# SRM32_Pi_HAT.net
KiCad netlist of a schematic drawn in Altium Designer
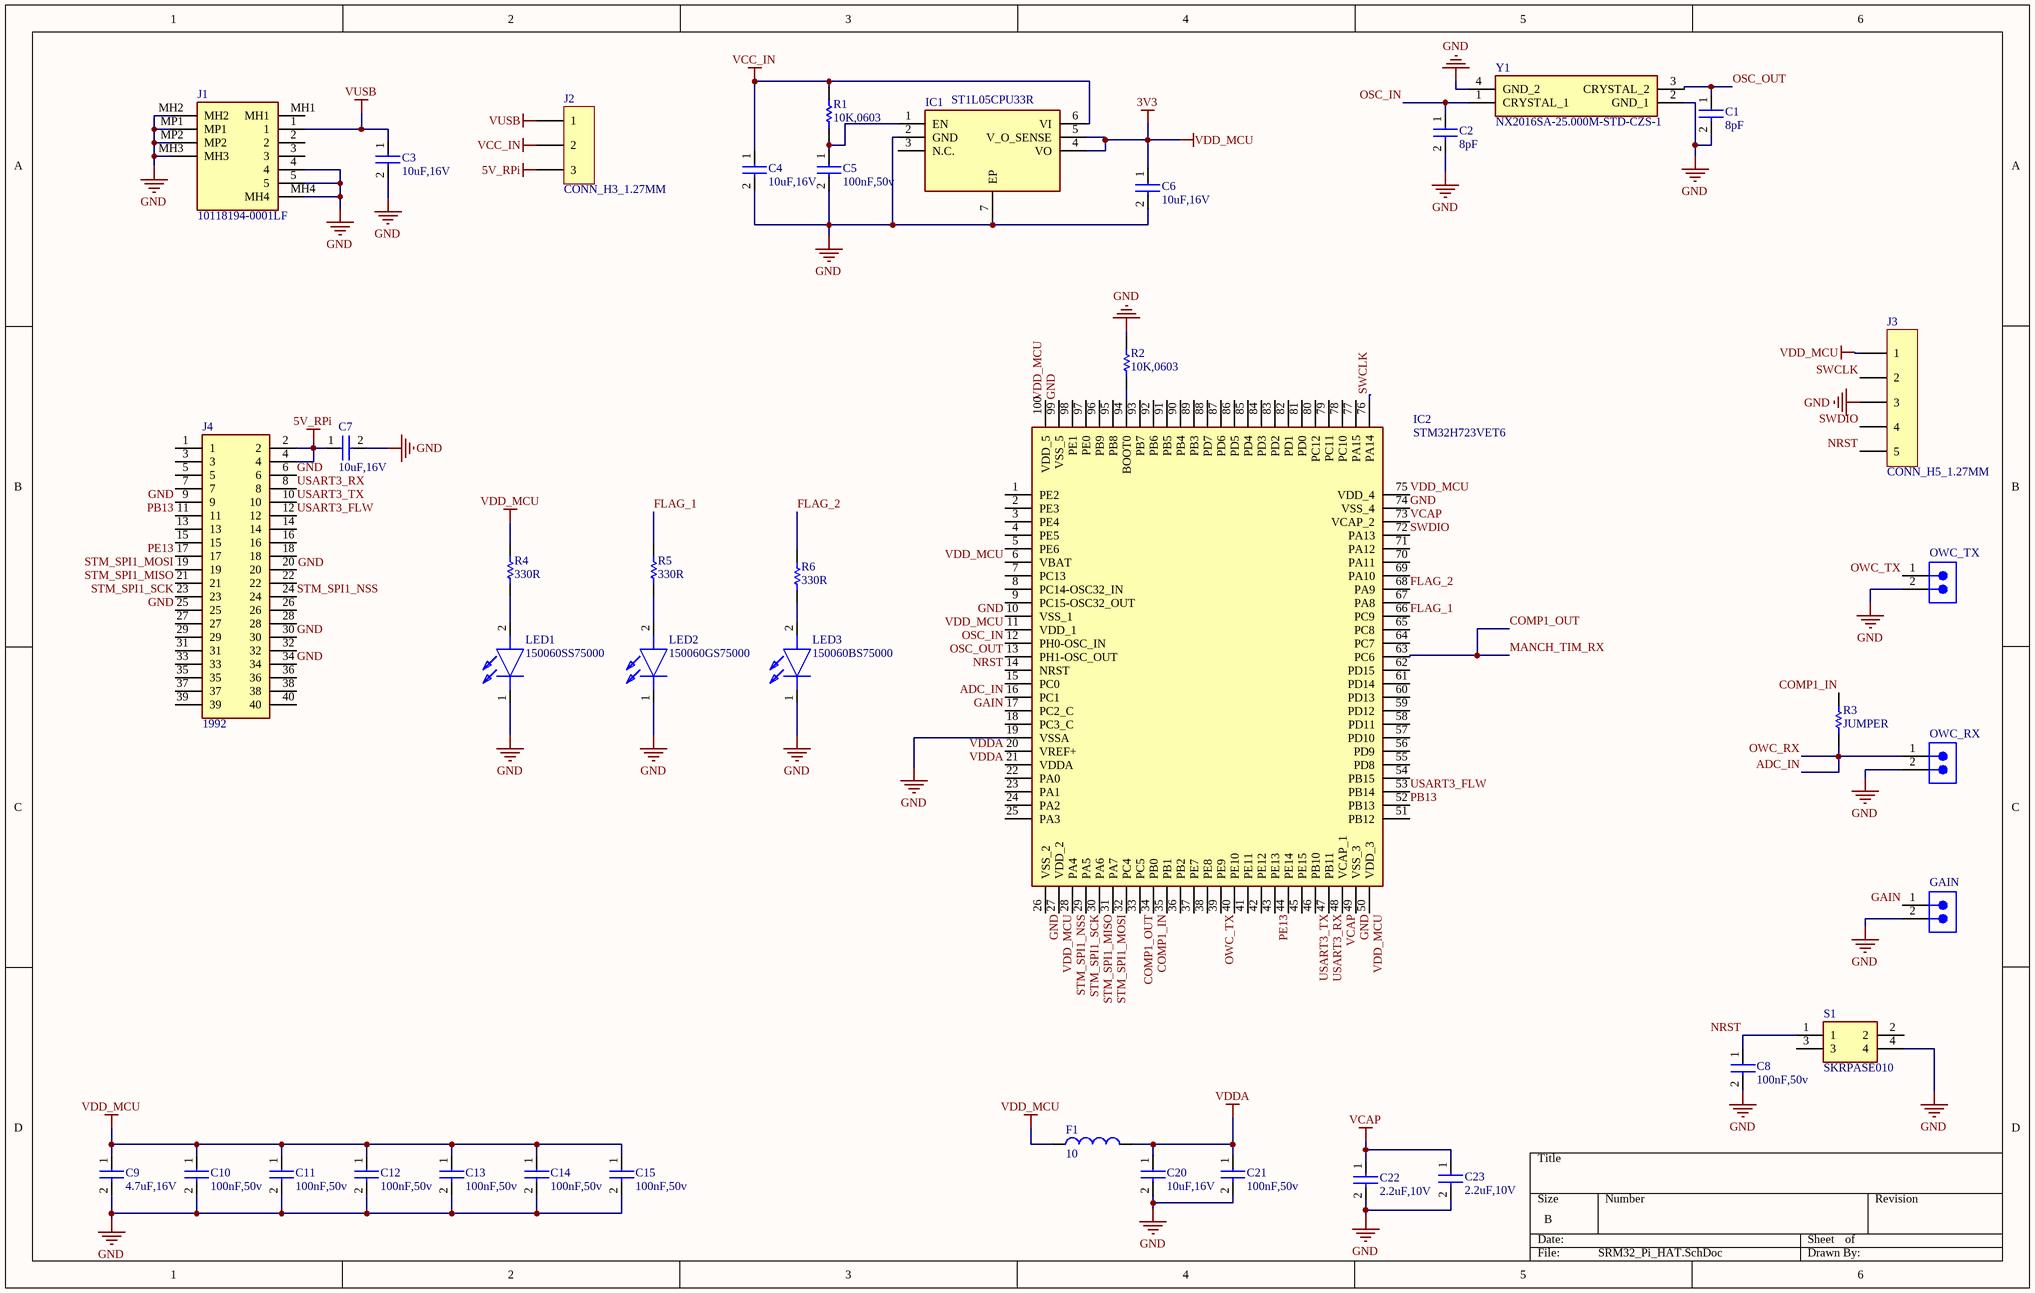
[diagram p0: SRM32_Pi_HAT.SchDoc]

(export (version "E")
  (design (tool "Eeschema 10.0.6"))
  (components
    (comp (ref "C1")
      (value "8pF")
      (footprint "CAP0603_")
      (description "Multilayer Ceramic Capacitors MLCC - SMD/SMT WCAP-CSGP 100V 4.7pF 0603 .25pFTol")
      (libsource (lib "RLC_COMPONENTS") (part "C0603-4.7pF-100v"))
    )
    (comp (ref "C2")
      (value "8pF")
      (footprint "CAP0603_")
      (description "Multilayer Ceramic Capacitors MLCC - SMD/SMT WCAP-CSGP 100V 4.7pF 0603 .25pFTol")
      (libsource (lib "RLC_COMPONENTS") (part "C0603-4.7pF-100v"))
    )
    (comp (ref "C3")
      (value "10uF,16V")
      (footprint "CAP0603_")
      (description "SMD/SMT 10uF 0603 10% 16V MLCC")
      (libsource (lib "RLC_COMPONENTS") (part "C0603-10uF-16v"))
    )
    (comp (ref "C4")
      (value "10uF,16V")
      (footprint "CAP0603_")
      (description "SMD/SMT 10uF 0603 10% 16V MLCC")
      (libsource (lib "RLC_COMPONENTS") (part "C0603-10uF-16v"))
    )
    (comp (ref "C5")
      (value "100nF,50v")
      (footprint "CAP0603_")
      (description "Capacitor, Ceramic, 10nF, 50V, 20%, X7R, 0603")
      (libsource (lib "RLC_COMPONENTS") (part "C0603-100nF-50V-X7R"))
    )
    (comp (ref "C6")
      (value "10uF,16V")
      (footprint "CAP0603_")
      (description "SMD/SMT 10uF 0603 10% 16V MLCC")
      (libsource (lib "RLC_COMPONENTS") (part "C0603-10uF-16v"))
    )
    (comp (ref "C7")
      (value "10uF,16V")
      (footprint "CAP0603_")
      (description "SMD/SMT 10uF 0603 10% 16V MLCC")
      (libsource (lib "RLC_COMPONENTS") (part "C0603-10uF-16v"))
    )
    (comp (ref "C8")
      (value "100nF,50v")
      (footprint "CAP0603_")
      (description "Capacitor, Ceramic, 10nF, 50V, 20%, X7R, 0603")
      (libsource (lib "RLC_COMPONENTS") (part "C0603-100nF-50V-X7R"))
    )
    (comp (ref "C9")
      (value "4.7uF,16V")
      (footprint "CAP0603_")
      (description "Multilayer Ceramic Capacitors MLCC - SMD/SMT 0603 16VDC 4.7uF 20% X5R")
      (libsource (lib "RLC_COMPONENTS") (part "C0603-4.7uF-16V-X5R"))
    )
    (comp (ref "C10")
      (value "100nF,50v")
      (footprint "CAP0603_")
      (description "Capacitor, Ceramic, 10nF, 50V, 20%, X7R, 0603")
      (libsource (lib "RLC_COMPONENTS") (part "C0603-100nF-50V-X7R"))
    )
    (comp (ref "C11")
      (value "100nF,50v")
      (footprint "CAP0603_")
      (description "Capacitor, Ceramic, 10nF, 50V, 20%, X7R, 0603")
      (libsource (lib "RLC_COMPONENTS") (part "C0603-100nF-50V-X7R"))
    )
    (comp (ref "C12")
      (value "100nF,50v")
      (footprint "CAP0603_")
      (description "Capacitor, Ceramic, 10nF, 50V, 20%, X7R, 0603")
      (libsource (lib "RLC_COMPONENTS") (part "C0603-100nF-50V-X7R"))
    )
    (comp (ref "C13")
      (value "100nF,50v")
      (footprint "CAP0603_")
      (description "Capacitor, Ceramic, 10nF, 50V, 20%, X7R, 0603")
      (libsource (lib "RLC_COMPONENTS") (part "C0603-100nF-50V-X7R"))
    )
    (comp (ref "C14")
      (value "100nF,50v")
      (footprint "CAP0603_")
      (description "Capacitor, Ceramic, 10nF, 50V, 20%, X7R, 0603")
      (libsource (lib "RLC_COMPONENTS") (part "C0603-100nF-50V-X7R"))
    )
    (comp (ref "C15")
      (value "100nF,50v")
      (footprint "CAP0603_")
      (description "Capacitor, Ceramic, 10nF, 50V, 20%, X7R, 0603")
      (libsource (lib "RLC_COMPONENTS") (part "C0603-100nF-50V-X7R"))
    )
    (comp (ref "C20")
      (value "10uF,16V")
      (footprint "CAP0603_")
      (description "SMD/SMT 10uF 0603 10% 16V MLCC")
      (libsource (lib "RLC_COMPONENTS") (part "C0603-10uF-16v"))
    )
    (comp (ref "C21")
      (value "100nF,50v")
      (footprint "CAP0603_")
      (description "Capacitor, Ceramic, 10nF, 50V, 20%, X7R, 0603")
      (libsource (lib "RLC_COMPONENTS") (part "C0603-100nF-50V-X7R"))
    )
    (comp (ref "C22")
      (value "2.2uF,10V")
      (footprint "CAP0603_")
      (description "Multilayer Ceramic Capacitors MLCC - SMD/SMT WCAP-CSGP 2.2uF 0603 20% 10V MLCC")
      (libsource (lib "RLC_COMPONENTS") (part "C0603-2.2uF-10V-X5R"))
    )
    (comp (ref "C23")
      (value "2.2uF,10V")
      (footprint "CAP0603_")
      (description "Multilayer Ceramic Capacitors MLCC - SMD/SMT WCAP-CSGP 2.2uF 0603 20% 10V MLCC")
      (libsource (lib "RLC_COMPONENTS") (part "C0603-2.2uF-10V-X5R"))
    )
    (comp (ref "F1")
      (value "10")
      (footprint "IND0603_")
      (description "Ferrite Beads 10 ohms 25% HIGH CURRENT 6A")
      (libsource (lib "RLC_COMPONENTS") (part "MH1608-100Y"))
    )
    (comp (ref "GAIN")
      (value "61900211121")
      (footprint "61900211121")
      (libsource (lib "Altium Content Vault") (part "Header_Male_1R_02P"))
    )
    (comp (ref "IC1")
      (value "ST1L05CPU33R")
      (footprint "SamacSys:SON95P300X300X100-7N-D")
      (description "Integrated Circuit")
      (fields (field (name "MOUSER PART NUMBER") "511-ST1L05CPU33R"))
      (libsource (lib "*") (part "ST1L05CPU33R"))
    )
    (comp (ref "IC2")
      (value "STM32H723VET6")
      (footprint "QFP50P1600X1600X160-100N")
      (description "Integrated Circuit")
      (fields (field (name "MOUSER PART NUMBER") "511-STM32H723VET6"))
      (libsource (lib "Fglopez Fglopez") (part "STM32H723VET6"))
    )
    (comp (ref "J1")
      (value "10118194-0001LF")
      (footprint "SamacSys:101181940001LF")
      (description "Connector")
      (libsource (lib "SamacSys") (part "10118194-0001LF"))
    )
    (comp (ref "J2")
      (value "CONN_H3_1.27MM")
      (footprint "CONN_H3_1.27MM")
      (libsource (lib "conectors") (part "CONN_H3_1.27MM"))
    )
    (comp (ref "J3")
      (value "CONN_H5_1.27MM")
      (footprint "CONN_H5_1.27MM")
      (libsource (lib "conectors") (part "CONN_H5_1.27MM"))
    )
    (comp (ref "J4")
      (value "1992")
      (footprint "SamacSys:RHDR40W64P254_2X20_5130X500X1375P")
      (description "Connector")
      (fields (field (name "MOUSER PART NUMBER") "485-1992"))
      (libsource (lib "*") (part "1992"))
    )
    (comp (ref "LED1")
      (value "150060SS75000")
      (footprint "SamacSys:LEDC1608X80N")
      (description "LED")
      (fields (field (name "MOUSER PART NUMBER") "710-150060SS75000"))
      (libsource (lib "*") (part "150060SS75000"))
    )
    (comp (ref "LED2")
      (value "150060GS75000")
      (footprint "SamacSys:LEDC1608X70N")
      (description "LED")
      (fields (field (name "MOUSER PART NUMBER") "710-150060GS75000"))
      (libsource (lib "*") (part "150060GS75000"))
    )
    (comp (ref "LED3")
      (value "150060BS75000")
      (footprint "SamacSys:LEDC1608X80N")
      (description "LED")
      (fields (field (name "MOUSER PART NUMBER") "710-150060BS75000"))
      (libsource (lib "*") (part "150060BS75000"))
    )
    (comp (ref "OWC_RX")
      (value "61900211121")
      (footprint "61900211121")
      (libsource (lib "Altium Content Vault") (part "Header_Male_1R_02P"))
    )
    (comp (ref "OWC_TX")
      (value "61900211121")
      (footprint "61900211121")
      (libsource (lib "Altium Content Vault") (part "Header_Male_1R_02P"))
    )
    (comp (ref "R1")
      (value "10K,0603")
      (footprint "RES0603_")
      (description "Thick Film Resistors - SMD 10K OHM 1% 0603")
      (libsource (lib "RLC_COMPONENTS") (part "R0603-10K-1/10W-1%"))
    )
    (comp (ref "R2")
      (value "10K,0603")
      (footprint "RES0603_")
      (description "Thick Film Resistors - SMD 10K OHM 1% 0603")
      (libsource (lib "RLC_COMPONENTS") (part "R0603-10K-1/10W-1%"))
    )
    (comp (ref "R3")
      (value "JUMPER")
      (footprint "RES0603_")
      (description "Resistor, ThinFilm, 0R, 5%, 1/8W, 0603")
      (libsource (lib "RLC_COMPONENTS") (part "R0603-0R-1/10W-5%"))
    )
    (comp (ref "R4")
      (value "330R")
      (footprint "RES0603_")
      (description "Thick Film Resistors - SMD 330Ohmns 1/10W 0603 5%")
      (libsource (lib "RLC_COMPONENTS") (part "R0603-330R-1/10W-1%_1"))
    )
    (comp (ref "R5")
      (value "330R")
      (footprint "RES0603_")
      (description "Thick Film Resistors - SMD 330Ohmns 1/10W 0603 5%")
      (libsource (lib "RLC_COMPONENTS") (part "R0603-330R-1/10W-1%_1"))
    )
    (comp (ref "R6")
      (value "330R")
      (footprint "RES0603_")
      (description "Thick Film Resistors - SMD 330Ohmns 1/10W 0603 5%")
      (libsource (lib "RLC_COMPONENTS") (part "R0603-330R-1/10W-1%_1"))
    )
    (comp (ref "S1")
      (value "SKRPASE010")
      (footprint "SamacSys:SKRPASE010")
      (description "Switch")
      (fields (field (name "MOUSER PART NUMBER") "688-SKRPASE010"))
      (libsource (lib "SamacSys") (part "SKRPASE010"))
    )
    (comp (ref "Y1")
      (value "NX2016SA-25.000M-STD-CZS-1")
      (footprint "SamacSys:NX2016SA32MEXS00ACS06465")
      (description "Crystal or Oscillator")
      (fields (field (name "MOUSER PART NUMBER") "344-NX2016SA25MSTZS1"))
      (libsource (lib "SamacSys") (part "NX2016SA-25.000M-STD-CZS-1"))
    )
  )
  (nets
    (net (code "2") (name "/ADC_IN") (class "Default")
      (node (ref "IC2") (pin "16") (pinfunction "PC1_16") (pintype "passive"))
      (node (ref "OWC_RX") (pin "1") (pinfunction "1_1") (pintype "passive"))
      (node (ref "R3") (pin "1") (pinfunction "1_1") (pintype "passive"))
    )
    (net (code "3") (name "/COMP1_IN") (class "Default")
      (node (ref "IC2") (pin "34") (pinfunction "PB0_34") (pintype "passive"))
      (node (ref "R3") (pin "2") (pinfunction "2_2") (pintype "passive"))
    )
    (net (code "4") (name "/COMP1_OUT") (class "Default")
      (node (ref "IC2") (pin "33") (pinfunction "PC5_33") (pintype "passive"))
      (node (ref "IC2") (pin "63") (pinfunction "PC6_63") (pintype "passive"))
    )
    (net (code "5") (name "/FLAG_1") (class "Default")
      (node (ref "IC2") (pin "66") (pinfunction "PC9_66") (pintype "passive"))
      (node (ref "R5") (pin "1") (pinfunction "1_1") (pintype "passive"))
    )
    (net (code "6") (name "/FLAG_2") (class "Default")
      (node (ref "IC2") (pin "68") (pinfunction "PA9_68") (pintype "passive"))
      (node (ref "R6") (pin "1") (pinfunction "1_1") (pintype "passive"))
    )
    (net (code "7") (name "/GAIN") (class "Default")
      (node (ref "GAIN") (pin "1") (pinfunction "1_1") (pintype "passive"))
      (node (ref "IC2") (pin "17") (pinfunction "PC2_C_17") (pintype "passive"))
    )
    (net (code "8") (name "/NRST") (class "Default")
      (node (ref "C8") (pin "1") (pinfunction "1_1") (pintype "passive"))
      (node (ref "IC2") (pin "14") (pinfunction "NRST_14") (pintype "passive"))
      (node (ref "J3") (pin "5") (pinfunction "5_5") (pintype "passive"))
      (node (ref "S1") (pin "1") (pinfunction "1_1") (pintype "passive"))
    )
    (net (code "9") (name "/OSC_IN") (class "Default")
      (node (ref "C2") (pin "1") (pinfunction "1_1") (pintype "passive"))
      (node (ref "IC2") (pin "12") (pinfunction "PH0-OSC_IN_12") (pintype "passive"))
      (node (ref "Y1") (pin "1") (pinfunction "CRYSTAL_1_1") (pintype "passive"))
    )
    (net (code "10") (name "/OSC_OUT") (class "Default")
      (node (ref "C1") (pin "1") (pinfunction "1_1") (pintype "passive"))
      (node (ref "IC2") (pin "13") (pinfunction "PH1-OSC_OUT_13") (pintype "passive"))
      (node (ref "Y1") (pin "3") (pinfunction "CRYSTAL_2_3") (pintype "passive"))
    )
    (net (code "11") (name "/OWC_TX") (class "Default")
      (node (ref "IC2") (pin "39") (pinfunction "PE9_39") (pintype "passive"))
      (node (ref "OWC_TX") (pin "1") (pinfunction "1_1") (pintype "passive"))
    )
    (net (code "12") (name "/PB13") (class "Default")
      (node (ref "IC2") (pin "52") (pinfunction "PB13_52") (pintype "passive"))
      (node (ref "J4") (pin "11") (pinfunction "11_11") (pintype "passive"))
    )
    (net (code "13") (name "/PE13") (class "Default")
      (node (ref "IC2") (pin "43") (pinfunction "PE13_43") (pintype "passive"))
      (node (ref "J4") (pin "17") (pinfunction "17_17") (pintype "passive"))
    )
    (net (code "14") (name "/STM_SPI1_MISO") (class "Default")
      (node (ref "IC2") (pin "30") (pinfunction "PA6_30") (pintype "passive"))
      (node (ref "J4") (pin "21") (pinfunction "21_21") (pintype "passive"))
    )
    (net (code "15") (name "/STM_SPI1_MOSI") (class "Default")
      (node (ref "IC2") (pin "31") (pinfunction "PA7_31") (pintype "passive"))
      (node (ref "J4") (pin "19") (pinfunction "19_19") (pintype "passive"))
    )
    (net (code "16") (name "/STM_SPI1_NSS") (class "Default")
      (node (ref "IC2") (pin "28") (pinfunction "PA4_28") (pintype "passive"))
      (node (ref "J4") (pin "24") (pinfunction "24_24") (pintype "passive"))
    )
    (net (code "17") (name "/STM_SPI1_SCK") (class "Default")
      (node (ref "IC2") (pin "29") (pinfunction "PA5_29") (pintype "passive"))
      (node (ref "J4") (pin "23") (pinfunction "23_23") (pintype "passive"))
    )
    (net (code "18") (name "/SWCLK") (class "Default")
      (node (ref "IC2") (pin "76") (pinfunction "PA14_76") (pintype "passive"))
      (node (ref "J3") (pin "2") (pinfunction "2_2") (pintype "passive"))
    )
    (net (code "19") (name "/SWDIO") (class "Default")
      (node (ref "IC2") (pin "72") (pinfunction "PA13_72") (pintype "passive"))
      (node (ref "J3") (pin "4") (pinfunction "4_4") (pintype "passive"))
    )
    (net (code "20") (name "/USART3_FLW") (class "Default")
      (node (ref "IC2") (pin "53") (pinfunction "PB14_53") (pintype "passive"))
      (node (ref "J4") (pin "12") (pinfunction "12_12") (pintype "passive"))
    )
    (net (code "21") (name "/USART3_RX") (class "Default")
      (node (ref "IC2") (pin "47") (pinfunction "PB11_47") (pintype "passive"))
      (node (ref "J4") (pin "8") (pinfunction "8_8") (pintype "passive"))
    )
    (net (code "22") (name "/USART3_TX") (class "Default")
      (node (ref "IC2") (pin "46") (pinfunction "PB10_46") (pintype "passive"))
      (node (ref "J4") (pin "10") (pinfunction "10_10") (pintype "passive"))
    )
    (net (code "23") (name "3V3") (class "Default")
      (node (ref "C10") (pin "1") (pinfunction "1_1") (pintype "passive"))
      (node (ref "C11") (pin "1") (pinfunction "1_1") (pintype "passive"))
      (node (ref "C12") (pin "1") (pinfunction "1_1") (pintype "passive"))
      (node (ref "C13") (pin "1") (pinfunction "1_1") (pintype "passive"))
      (node (ref "C14") (pin "1") (pinfunction "1_1") (pintype "passive"))
      (node (ref "C15") (pin "1") (pinfunction "1_1") (pintype "passive"))
      (node (ref "C6") (pin "1") (pinfunction "1_1") (pintype "passive"))
      (node (ref "C9") (pin "1") (pinfunction "1_1") (pintype "passive"))
      (node (ref "F1") (pin "1") (pinfunction "1_1") (pintype "passive"))
      (node (ref "IC1") (pin "4") (pinfunction "VO_4") (pintype "passive"))
      (node (ref "IC1") (pin "5") (pinfunction "V_O_SENSE_5") (pintype "passive"))
      (node (ref "IC2") (pin "100") (pinfunction "VDD_5_100") (pintype "passive"))
      (node (ref "IC2") (pin "11") (pinfunction "VDD_1_11") (pintype "passive"))
      (node (ref "IC2") (pin "27") (pinfunction "VDD_2_27") (pintype "passive"))
      (node (ref "IC2") (pin "50") (pinfunction "VDD_3_50") (pintype "passive"))
      (node (ref "IC2") (pin "6") (pinfunction "VBAT_6") (pintype "passive"))
      (node (ref "IC2") (pin "75") (pinfunction "VDD_4_75") (pintype "passive"))
      (node (ref "J3") (pin "1") (pinfunction "1_1") (pintype "passive"))
      (node (ref "R4") (pin "1") (pinfunction "1_1") (pintype "passive"))
    )
    (net (code "24") (name "5V_RPi") (class "Default")
      (node (ref "C7") (pin "1") (pinfunction "1_1") (pintype "passive"))
      (node (ref "J2") (pin "3") (pinfunction "3_3") (pintype "passive"))
      (node (ref "J4") (pin "2") (pinfunction "2_2") (pintype "passive"))
      (node (ref "J4") (pin "4") (pinfunction "4_4") (pintype "passive"))
    )
    (net (code "25") (name "GND") (class "Default")
      (node (ref "C1") (pin "2") (pinfunction "2_2") (pintype "passive"))
      (node (ref "C10") (pin "2") (pinfunction "2_2") (pintype "passive"))
      (node (ref "C11") (pin "2") (pinfunction "2_2") (pintype "passive"))
      (node (ref "C12") (pin "2") (pinfunction "2_2") (pintype "passive"))
      (node (ref "C13") (pin "2") (pinfunction "2_2") (pintype "passive"))
      (node (ref "C14") (pin "2") (pinfunction "2_2") (pintype "passive"))
      (node (ref "C15") (pin "2") (pinfunction "2_2") (pintype "passive"))
      (node (ref "C2") (pin "2") (pinfunction "2_2") (pintype "passive"))
      (node (ref "C20") (pin "2") (pinfunction "2_2") (pintype "passive"))
      (node (ref "C21") (pin "2") (pinfunction "2_2") (pintype "passive"))
      (node (ref "C22") (pin "2") (pinfunction "2_2") (pintype "passive"))
      (node (ref "C23") (pin "2") (pinfunction "2_2") (pintype "passive"))
      (node (ref "C3") (pin "2") (pinfunction "2_2") (pintype "passive"))
      (node (ref "C4") (pin "2") (pinfunction "2_2") (pintype "passive"))
      (node (ref "C5") (pin "2") (pinfunction "2_2") (pintype "passive"))
      (node (ref "C6") (pin "2") (pinfunction "2_2") (pintype "passive"))
      (node (ref "C7") (pin "2") (pinfunction "2_2") (pintype "passive"))
      (node (ref "C8") (pin "2") (pinfunction "2_2") (pintype "passive"))
      (node (ref "C9") (pin "2") (pinfunction "2_2") (pintype "passive"))
      (node (ref "GAIN") (pin "2") (pinfunction "2_2") (pintype "passive"))
      (node (ref "IC1") (pin "2") (pinfunction "GND_2") (pintype "passive"))
      (node (ref "IC1") (pin "7") (pinfunction "EP_7") (pintype "passive"))
      (node (ref "IC2") (pin "10") (pinfunction "VSS_1_10") (pintype "passive"))
      (node (ref "IC2") (pin "19") (pinfunction "VSSA_19") (pintype "passive"))
      (node (ref "IC2") (pin "26") (pinfunction "VSS_2_26") (pintype "passive"))
      (node (ref "IC2") (pin "49") (pinfunction "VSS_3_49") (pintype "passive"))
      (node (ref "IC2") (pin "74") (pinfunction "VSS_4_74") (pintype "passive"))
      (node (ref "IC2") (pin "99") (pinfunction "VSS_5_99") (pintype "passive"))
      (node (ref "J1") (pin "4") (pinfunction "4_4") (pintype "passive"))
      (node (ref "J1") (pin "5") (pinfunction "5_5") (pintype "passive"))
      (node (ref "J1") (pin "MH2") (pinfunction "MH2_MH2") (pintype "passive"))
      (node (ref "J1") (pin "MH3") (pinfunction "MH3_MH3") (pintype "passive"))
      (node (ref "J1") (pin "MH4") (pinfunction "MH4_MH4") (pintype "passive"))
      (node (ref "J1") (pin "MP1") (pinfunction "MP1_MP1") (pintype "passive"))
      (node (ref "J1") (pin "MP2") (pinfunction "MP2_MP2") (pintype "passive"))
      (node (ref "J3") (pin "3") (pinfunction "3_3") (pintype "passive"))
      (node (ref "J4") (pin "25") (pinfunction "25_25") (pintype "passive"))
      (node (ref "J4") (pin "30") (pinfunction "30_30") (pintype "passive"))
      (node (ref "J4") (pin "34") (pinfunction "34_34") (pintype "passive"))
      (node (ref "J4") (pin "6") (pinfunction "6_6") (pintype "passive"))
      (node (ref "J4") (pin "9") (pinfunction "9_9") (pintype "passive"))
      (node (ref "LED1") (pin "1") (pinfunction "K_1") (pintype "passive"))
      (node (ref "LED2") (pin "1") (pinfunction "K_1") (pintype "passive"))
      (node (ref "LED3") (pin "1") (pinfunction "K_1") (pintype "passive"))
      (node (ref "OWC_RX") (pin "2") (pinfunction "2_2") (pintype "passive"))
      (node (ref "OWC_TX") (pin "2") (pinfunction "2_2") (pintype "passive"))
      (node (ref "R2") (pin "1") (pinfunction "1_1") (pintype "passive"))
      (node (ref "S1") (pin "4") (pinfunction "4_4") (pintype "passive"))
      (node (ref "Y1") (pin "2") (pinfunction "GND_1_2") (pintype "passive"))
      (node (ref "Y1") (pin "4") (pinfunction "GND_2_4") (pintype "passive"))
    )
    (net (code "26") (name "Net-(IC1-EN)") (class "Default")
      (node (ref "C5") (pin "1") (pinfunction "1_1") (pintype "passive"))
      (node (ref "IC1") (pin "1") (pinfunction "EN_1") (pintype "passive"))
      (node (ref "R1") (pin "2") (pinfunction "2_2") (pintype "passive"))
    )
    (net (code "27") (name "Net-(IC2-BOOT0)") (class "Default")
      (node (ref "IC2") (pin "94") (pinfunction "BOOT0_94") (pintype "passive"))
      (node (ref "R2") (pin "2") (pinfunction "2_2") (pintype "passive"))
    )
    (net (code "28") (name "Net-(LED1-A)") (class "Default")
      (node (ref "LED1") (pin "2") (pinfunction "A_2") (pintype "passive"))
      (node (ref "R4") (pin "2") (pinfunction "2_2") (pintype "passive"))
    )
    (net (code "29") (name "Net-(LED2-A)") (class "Default")
      (node (ref "LED2") (pin "2") (pinfunction "A_2") (pintype "passive"))
      (node (ref "R5") (pin "2") (pinfunction "2_2") (pintype "passive"))
    )
    (net (code "30") (name "Net-(LED3-A)") (class "Default")
      (node (ref "LED3") (pin "2") (pinfunction "A_2") (pintype "passive"))
      (node (ref "R6") (pin "2") (pinfunction "2_2") (pintype "passive"))
    )
    (net (code "31") (name "VCAP") (class "Default")
      (node (ref "C22") (pin "1") (pinfunction "1_1") (pintype "passive"))
      (node (ref "C23") (pin "1") (pinfunction "1_1") (pintype "passive"))
      (node (ref "IC2") (pin "48") (pinfunction "VCAP_1_48") (pintype "passive"))
      (node (ref "IC2") (pin "73") (pinfunction "VCAP_2_73") (pintype "passive"))
    )
    (net (code "32") (name "VCC_IN") (class "Default")
      (node (ref "C4") (pin "1") (pinfunction "1_1") (pintype "passive"))
      (node (ref "IC1") (pin "6") (pinfunction "VI_6") (pintype "passive"))
      (node (ref "J2") (pin "2") (pinfunction "2_2") (pintype "passive"))
      (node (ref "R1") (pin "1") (pinfunction "1_1") (pintype "passive"))
    )
    (net (code "33") (name "VDDA") (class "Default")
      (node (ref "C20") (pin "1") (pinfunction "1_1") (pintype "passive"))
      (node (ref "C21") (pin "1") (pinfunction "1_1") (pintype "passive"))
      (node (ref "F1") (pin "2") (pinfunction "2_2") (pintype "passive"))
      (node (ref "IC2") (pin "20") (pinfunction "VREF+_20") (pintype "passive"))
      (node (ref "IC2") (pin "21") (pinfunction "VDDA_21") (pintype "passive"))
    )
    (net (code "34") (name "VUSB") (class "Default")
      (node (ref "C3") (pin "1") (pinfunction "1_1") (pintype "passive"))
      (node (ref "J1") (pin "1") (pinfunction "1_1") (pintype "passive"))
      (node (ref "J2") (pin "1") (pinfunction "1_1") (pintype "passive"))
    )
    (net (code "35") (name "unconnected-(IC1-N.C.-Pad3)") (class "Default")
      (node (ref "IC1") (pin "3") (pinfunction "N.C._3") (pintype "passive"))
    )
    (net (code "36") (name "unconnected-(IC2-PA0-Pad22)") (class "Default")
      (node (ref "IC2") (pin "22") (pinfunction "PA0_22") (pintype "passive"))
    )
    (net (code "37") (name "unconnected-(IC2-PA1-Pad23)") (class "Default")
      (node (ref "IC2") (pin "23") (pinfunction "PA1_23") (pintype "passive"))
    )
    (net (code "38") (name "unconnected-(IC2-PA2-Pad24)") (class "Default")
      (node (ref "IC2") (pin "24") (pinfunction "PA2_24") (pintype "passive"))
    )
    (net (code "39") (name "unconnected-(IC2-PA3-Pad25)") (class "Default")
      (node (ref "IC2") (pin "25") (pinfunction "PA3_25") (pintype "passive"))
    )
    (net (code "40") (name "unconnected-(IC2-PA8-Pad67)") (class "Default")
      (node (ref "IC2") (pin "67") (pinfunction "PA8_67") (pintype "passive"))
    )
    (net (code "41") (name "unconnected-(IC2-PA10-Pad69)") (class "Default")
      (node (ref "IC2") (pin "69") (pinfunction "PA10_69") (pintype "passive"))
    )
    (net (code "42") (name "unconnected-(IC2-PA11-Pad70)") (class "Default")
      (node (ref "IC2") (pin "70") (pinfunction "PA11_70") (pintype "passive"))
    )
    (net (code "43") (name "unconnected-(IC2-PA12-Pad71)") (class "Default")
      (node (ref "IC2") (pin "71") (pinfunction "PA12_71") (pintype "passive"))
    )
    (net (code "44") (name "unconnected-(IC2-PA15-Pad77)") (class "Default")
      (node (ref "IC2") (pin "77") (pinfunction "PA15_77") (pintype "passive"))
    )
    (net (code "45") (name "unconnected-(IC2-PB1-Pad35)") (class "Default")
      (node (ref "IC2") (pin "35") (pinfunction "PB1_35") (pintype "passive"))
    )
    (net (code "46") (name "unconnected-(IC2-PB2-Pad36)") (class "Default")
      (node (ref "IC2") (pin "36") (pinfunction "PB2_36") (pintype "passive"))
    )
    (net (code "47") (name "unconnected-(IC2-PB3-Pad89)") (class "Default")
      (node (ref "IC2") (pin "89") (pinfunction "PB3_89") (pintype "passive"))
    )
    (net (code "48") (name "unconnected-(IC2-PB4-Pad90)") (class "Default")
      (node (ref "IC2") (pin "90") (pinfunction "PB4_90") (pintype "passive"))
    )
    (net (code "49") (name "unconnected-(IC2-PB5-Pad91)") (class "Default")
      (node (ref "IC2") (pin "91") (pinfunction "PB5_91") (pintype "passive"))
    )
    (net (code "50") (name "unconnected-(IC2-PB6-Pad92)") (class "Default")
      (node (ref "IC2") (pin "92") (pinfunction "PB6_92") (pintype "passive"))
    )
    (net (code "51") (name "unconnected-(IC2-PB7-Pad93)") (class "Default")
      (node (ref "IC2") (pin "93") (pinfunction "PB7_93") (pintype "passive"))
    )
    (net (code "52") (name "unconnected-(IC2-PB8-Pad95)") (class "Default")
      (node (ref "IC2") (pin "95") (pinfunction "PB8_95") (pintype "passive"))
    )
    (net (code "53") (name "unconnected-(IC2-PB9-Pad96)") (class "Default")
      (node (ref "IC2") (pin "96") (pinfunction "PB9_96") (pintype "passive"))
    )
    (net (code "54") (name "unconnected-(IC2-PB12-Pad51)") (class "Default")
      (node (ref "IC2") (pin "51") (pinfunction "PB12_51") (pintype "passive"))
    )
    (net (code "55") (name "unconnected-(IC2-PB15-Pad54)") (class "Default")
      (node (ref "IC2") (pin "54") (pinfunction "PB15_54") (pintype "passive"))
    )
    (net (code "56") (name "unconnected-(IC2-PC0-Pad15)") (class "Default")
      (node (ref "IC2") (pin "15") (pinfunction "PC0_15") (pintype "passive"))
    )
    (net (code "57") (name "unconnected-(IC2-PC3_C-Pad18)") (class "Default")
      (node (ref "IC2") (pin "18") (pinfunction "PC3_C_18") (pintype "passive"))
    )
    (net (code "58") (name "unconnected-(IC2-PC4-Pad32)") (class "Default")
      (node (ref "IC2") (pin "32") (pinfunction "PC4_32") (pintype "passive"))
    )
    (net (code "59") (name "unconnected-(IC2-PC7-Pad64)") (class "Default")
      (node (ref "IC2") (pin "64") (pinfunction "PC7_64") (pintype "passive"))
    )
    (net (code "60") (name "unconnected-(IC2-PC8-Pad65)") (class "Default")
      (node (ref "IC2") (pin "65") (pinfunction "PC8_65") (pintype "passive"))
    )
    (net (code "61") (name "unconnected-(IC2-PC10-Pad78)") (class "Default")
      (node (ref "IC2") (pin "78") (pinfunction "PC10_78") (pintype "passive"))
    )
    (net (code "62") (name "unconnected-(IC2-PC11-Pad79)") (class "Default")
      (node (ref "IC2") (pin "79") (pinfunction "PC11_79") (pintype "passive"))
    )
    (net (code "63") (name "unconnected-(IC2-PC12-Pad80)") (class "Default")
      (node (ref "IC2") (pin "80") (pinfunction "PC12_80") (pintype "passive"))
    )
    (net (code "64") (name "unconnected-(IC2-PC13-Pad7)") (class "Default")
      (node (ref "IC2") (pin "7") (pinfunction "PC13_7") (pintype "passive"))
    )
    (net (code "65") (name "unconnected-(IC2-PC14-OSC32_IN-Pad8)") (class "Default")
      (node (ref "IC2") (pin "8") (pinfunction "PC14-OSC32_IN_8") (pintype "passive"))
    )
    (net (code "66") (name "unconnected-(IC2-PC15-OSC32_OUT-Pad9)") (class "Default")
      (node (ref "IC2") (pin "9") (pinfunction "PC15-OSC32_OUT_9") (pintype "passive"))
    )
    (net (code "67") (name "unconnected-(IC2-PD0-Pad81)") (class "Default")
      (node (ref "IC2") (pin "81") (pinfunction "PD0_81") (pintype "passive"))
    )
    (net (code "68") (name "unconnected-(IC2-PD1-Pad82)") (class "Default")
      (node (ref "IC2") (pin "82") (pinfunction "PD1_82") (pintype "passive"))
    )
    (net (code "69") (name "unconnected-(IC2-PD2-Pad83)") (class "Default")
      (node (ref "IC2") (pin "83") (pinfunction "PD2_83") (pintype "passive"))
    )
    (net (code "70") (name "unconnected-(IC2-PD3-Pad84)") (class "Default")
      (node (ref "IC2") (pin "84") (pinfunction "PD3_84") (pintype "passive"))
    )
    (net (code "71") (name "unconnected-(IC2-PD4-Pad85)") (class "Default")
      (node (ref "IC2") (pin "85") (pinfunction "PD4_85") (pintype "passive"))
    )
    (net (code "72") (name "unconnected-(IC2-PD5-Pad86)") (class "Default")
      (node (ref "IC2") (pin "86") (pinfunction "PD5_86") (pintype "passive"))
    )
    (net (code "73") (name "unconnected-(IC2-PD6-Pad87)") (class "Default")
      (node (ref "IC2") (pin "87") (pinfunction "PD6_87") (pintype "passive"))
    )
    (net (code "74") (name "unconnected-(IC2-PD7-Pad88)") (class "Default")
      (node (ref "IC2") (pin "88") (pinfunction "PD7_88") (pintype "passive"))
    )
    (net (code "75") (name "unconnected-(IC2-PD8-Pad55)") (class "Default")
      (node (ref "IC2") (pin "55") (pinfunction "PD8_55") (pintype "passive"))
    )
    (net (code "76") (name "unconnected-(IC2-PD9-Pad56)") (class "Default")
      (node (ref "IC2") (pin "56") (pinfunction "PD9_56") (pintype "passive"))
    )
    (net (code "77") (name "unconnected-(IC2-PD10-Pad57)") (class "Default")
      (node (ref "IC2") (pin "57") (pinfunction "PD10_57") (pintype "passive"))
    )
    (net (code "78") (name "unconnected-(IC2-PD11-Pad58)") (class "Default")
      (node (ref "IC2") (pin "58") (pinfunction "PD11_58") (pintype "passive"))
    )
    (net (code "79") (name "unconnected-(IC2-PD12-Pad59)") (class "Default")
      (node (ref "IC2") (pin "59") (pinfunction "PD12_59") (pintype "passive"))
    )
    (net (code "80") (name "unconnected-(IC2-PD13-Pad60)") (class "Default")
      (node (ref "IC2") (pin "60") (pinfunction "PD13_60") (pintype "passive"))
    )
    (net (code "81") (name "unconnected-(IC2-PD14-Pad61)") (class "Default")
      (node (ref "IC2") (pin "61") (pinfunction "PD14_61") (pintype "passive"))
    )
    (net (code "82") (name "unconnected-(IC2-PD15-Pad62)") (class "Default")
      (node (ref "IC2") (pin "62") (pinfunction "PD15_62") (pintype "passive"))
    )
    (net (code "83") (name "unconnected-(IC2-PE0-Pad97)") (class "Default")
      (node (ref "IC2") (pin "97") (pinfunction "PE0_97") (pintype "passive"))
    )
    (net (code "84") (name "unconnected-(IC2-PE1-Pad98)") (class "Default")
      (node (ref "IC2") (pin "98") (pinfunction "PE1_98") (pintype "passive"))
    )
    (net (code "85") (name "unconnected-(IC2-PE2-Pad1)") (class "Default")
      (node (ref "IC2") (pin "1") (pinfunction "PE2_1") (pintype "passive"))
    )
    (net (code "86") (name "unconnected-(IC2-PE3-Pad2)") (class "Default")
      (node (ref "IC2") (pin "2") (pinfunction "PE3_2") (pintype "passive"))
    )
    (net (code "87") (name "unconnected-(IC2-PE4-Pad3)") (class "Default")
      (node (ref "IC2") (pin "3") (pinfunction "PE4_3") (pintype "passive"))
    )
    (net (code "88") (name "unconnected-(IC2-PE5-Pad4)") (class "Default")
      (node (ref "IC2") (pin "4") (pinfunction "PE5_4") (pintype "passive"))
    )
    (net (code "89") (name "unconnected-(IC2-PE6-Pad5)") (class "Default")
      (node (ref "IC2") (pin "5") (pinfunction "PE6_5") (pintype "passive"))
    )
    (net (code "90") (name "unconnected-(IC2-PE7-Pad37)") (class "Default")
      (node (ref "IC2") (pin "37") (pinfunction "PE7_37") (pintype "passive"))
    )
    (net (code "91") (name "unconnected-(IC2-PE8-Pad38)") (class "Default")
      (node (ref "IC2") (pin "38") (pinfunction "PE8_38") (pintype "passive"))
    )
    (net (code "92") (name "unconnected-(IC2-PE10-Pad40)") (class "Default")
      (node (ref "IC2") (pin "40") (pinfunction "PE10_40") (pintype "passive"))
    )
    (net (code "93") (name "unconnected-(IC2-PE11-Pad41)") (class "Default")
      (node (ref "IC2") (pin "41") (pinfunction "PE11_41") (pintype "passive"))
    )
    (net (code "94") (name "unconnected-(IC2-PE12-Pad42)") (class "Default")
      (node (ref "IC2") (pin "42") (pinfunction "PE12_42") (pintype "passive"))
    )
    (net (code "95") (name "unconnected-(IC2-PE14-Pad44)") (class "Default")
      (node (ref "IC2") (pin "44") (pinfunction "PE14_44") (pintype "passive"))
    )
    (net (code "96") (name "unconnected-(IC2-PE15-Pad45)") (class "Default")
      (node (ref "IC2") (pin "45") (pinfunction "PE15_45") (pintype "passive"))
    )
    (net (code "97") (name "unconnected-(J1-Pad2)") (class "Default")
      (node (ref "J1") (pin "2") (pinfunction "2_2") (pintype "passive"))
    )
    (net (code "98") (name "unconnected-(J1-Pad3)") (class "Default")
      (node (ref "J1") (pin "3") (pinfunction "3_3") (pintype "passive"))
    )
    (net (code "99") (name "unconnected-(J1-PadMH1)") (class "Default")
      (node (ref "J1") (pin "MH1") (pinfunction "MH1_MH1") (pintype "passive"))
    )
    (net (code "100") (name "unconnected-(J4-Pad1)") (class "Default")
      (node (ref "J4") (pin "1") (pinfunction "1_1") (pintype "passive"))
    )
    (net (code "101") (name "unconnected-(J4-Pad3)") (class "Default")
      (node (ref "J4") (pin "3") (pinfunction "3_3") (pintype "passive"))
    )
    (net (code "102") (name "unconnected-(J4-Pad5)") (class "Default")
      (node (ref "J4") (pin "5") (pinfunction "5_5") (pintype "passive"))
    )
    (net (code "103") (name "unconnected-(J4-Pad7)") (class "Default")
      (node (ref "J4") (pin "7") (pinfunction "7_7") (pintype "passive"))
    )
    (net (code "104") (name "unconnected-(J4-Pad13)") (class "Default")
      (node (ref "J4") (pin "13") (pinfunction "13_13") (pintype "passive"))
    )
    (net (code "105") (name "unconnected-(J4-Pad14)") (class "Default")
      (node (ref "J4") (pin "14") (pinfunction "14_14") (pintype "passive"))
    )
    (net (code "106") (name "unconnected-(J4-Pad15)") (class "Default")
      (node (ref "J4") (pin "15") (pinfunction "15_15") (pintype "passive"))
    )
    (net (code "107") (name "unconnected-(J4-Pad16)") (class "Default")
      (node (ref "J4") (pin "16") (pinfunction "16_16") (pintype "passive"))
    )
    (net (code "108") (name "unconnected-(J4-Pad18)") (class "Default")
      (node (ref "J4") (pin "18") (pinfunction "18_18") (pintype "passive"))
    )
    (net (code "109") (name "unconnected-(J4-Pad20)") (class "Default")
      (node (ref "J4") (pin "20") (pinfunction "20_20") (pintype "passive"))
    )
    (net (code "110") (name "unconnected-(J4-Pad22)") (class "Default")
      (node (ref "J4") (pin "22") (pinfunction "22_22") (pintype "passive"))
    )
    (net (code "111") (name "unconnected-(J4-Pad26)") (class "Default")
      (node (ref "J4") (pin "26") (pinfunction "26_26") (pintype "passive"))
    )
    (net (code "112") (name "unconnected-(J4-Pad27)") (class "Default")
      (node (ref "J4") (pin "27") (pinfunction "27_27") (pintype "passive"))
    )
    (net (code "113") (name "unconnected-(J4-Pad28)") (class "Default")
      (node (ref "J4") (pin "28") (pinfunction "28_28") (pintype "passive"))
    )
    (net (code "114") (name "unconnected-(J4-Pad29)") (class "Default")
      (node (ref "J4") (pin "29") (pinfunction "29_29") (pintype "passive"))
    )
    (net (code "115") (name "unconnected-(J4-Pad31)") (class "Default")
      (node (ref "J4") (pin "31") (pinfunction "31_31") (pintype "passive"))
    )
    (net (code "116") (name "unconnected-(J4-Pad32)") (class "Default")
      (node (ref "J4") (pin "32") (pinfunction "32_32") (pintype "passive"))
    )
    (net (code "117") (name "unconnected-(J4-Pad33)") (class "Default")
      (node (ref "J4") (pin "33") (pinfunction "33_33") (pintype "passive"))
    )
    (net (code "118") (name "unconnected-(J4-Pad35)") (class "Default")
      (node (ref "J4") (pin "35") (pinfunction "35_35") (pintype "passive"))
    )
    (net (code "119") (name "unconnected-(J4-Pad36)") (class "Default")
      (node (ref "J4") (pin "36") (pinfunction "36_36") (pintype "passive"))
    )
    (net (code "120") (name "unconnected-(J4-Pad37)") (class "Default")
      (node (ref "J4") (pin "37") (pinfunction "37_37") (pintype "passive"))
    )
    (net (code "121") (name "unconnected-(J4-Pad38)") (class "Default")
      (node (ref "J4") (pin "38") (pinfunction "38_38") (pintype "passive"))
    )
    (net (code "122") (name "unconnected-(J4-Pad39)") (class "Default")
      (node (ref "J4") (pin "39") (pinfunction "39_39") (pintype "passive"))
    )
    (net (code "123") (name "unconnected-(J4-Pad40)") (class "Default")
      (node (ref "J4") (pin "40") (pinfunction "40_40") (pintype "passive"))
    )
    (net (code "124") (name "unconnected-(S1-Pad2)") (class "Default")
      (node (ref "S1") (pin "2") (pinfunction "2_2") (pintype "passive"))
    )
    (net (code "125") (name "unconnected-(S1-Pad3)") (class "Default")
      (node (ref "S1") (pin "3") (pinfunction "3_3") (pintype "passive"))
    )
  )
)
